# RS485.net
KiCad netlist of a schematic drawn in Altium Designer
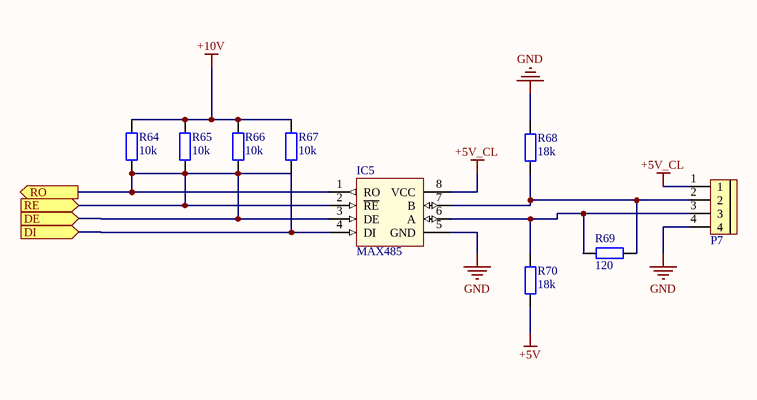
[diagram p0: RS485.SchDoc]

(export (version "E")
  (design (tool "Eeschema 10.0.6"))
  (components
    (comp (ref "IC5")
      (value "MAX485")
      (footprint "SO-8N")
      (description "RS232 - RS485 (Same sn75176)")
      (libsource (lib "My library altium") (part "MAX485"))
    )
    (comp (ref "P7")
      (value "CON 4 EDG5.08")
      (footprint "CON 4 4EDG5.08")
      (description "Cắm")
      (libsource (lib "Altium_Lib_by_KhueNguyenCreator") (part "CON 4 EDG5.08"))
    )
    (comp (ref "R64")
      (value "10k")
      (footprint "tro smd 0805")
      (description "Dán")
      (libsource (lib "Altium_Lib_by_KhueNguyenCreator") (part "Tro 0805 1% 10k"))
    )
    (comp (ref "R65")
      (value "10k")
      (footprint "tro smd 0805")
      (description "Dán")
      (libsource (lib "Altium_Lib_by_KhueNguyenCreator") (part "Tro 0805 1% 10k"))
    )
    (comp (ref "R66")
      (value "10k")
      (footprint "tro smd 0805")
      (description "Dán")
      (libsource (lib "Altium_Lib_by_KhueNguyenCreator") (part "Tro 0805 1% 10k"))
    )
    (comp (ref "R67")
      (value "10k")
      (footprint "tro smd 0805")
      (description "Dán")
      (libsource (lib "Altium_Lib_by_KhueNguyenCreator") (part "Tro 0805 1% 10k"))
    )
    (comp (ref "R68")
      (value "18k")
      (footprint "tro smd 0805")
      (description "Dán")
      (libsource (lib "Altium_Lib_by_KhueNguyenCreator") (part "Tro 0805 1% 18k"))
    )
    (comp (ref "R69")
      (value "120")
      (footprint "tro smd 0805")
      (description "Dán")
      (libsource (lib "Altium_Lib_by_KhueNguyenCreator") (part "Tro 0805 1% 12k"))
    )
    (comp (ref "R70")
      (value "18k")
      (footprint "tro smd 0805")
      (description "Dán")
      (libsource (lib "Altium_Lib_by_KhueNguyenCreator") (part "Tro 0805 1% 18k"))
    )
  )
  (nets
    (net (code "1") (name "+5V") (class "Default")
      (node (ref "R70") (pin "1") (pinfunction "1_1") (pintype "passive"))
    )
    (net (code "2") (name "+5V_CL") (class "Default")
      (node (ref "IC5") (pin "8") (pinfunction "VCC_8") (pintype "passive"))
      (node (ref "P7") (pin "1") (pinfunction "1_1") (pintype "passive"))
    )
    (net (code "3") (name "+10V") (class "Default")
      (node (ref "R64") (pin "2") (pinfunction "2_2") (pintype "passive"))
      (node (ref "R65") (pin "2") (pinfunction "2_2") (pintype "passive"))
      (node (ref "R66") (pin "2") (pinfunction "2_2") (pintype "passive"))
      (node (ref "R67") (pin "2") (pinfunction "2_2") (pintype "passive"))
    )
    (net (code "4") (name "/DE") (class "Default")
      (node (ref "IC5") (pin "1") (pinfunction "RO_1") (pintype "output"))
      (node (ref "IC5") (pin "2") (pinfunction "~{RE}_2") (pintype "input"))
      (node (ref "IC5") (pin "3") (pinfunction "DE_3") (pintype "input"))
      (node (ref "IC5") (pin "4") (pinfunction "DI_4") (pintype "input"))
      (node (ref "R64") (pin "1") (pinfunction "1_1") (pintype "passive"))
      (node (ref "R65") (pin "1") (pinfunction "1_1") (pintype "passive"))
      (node (ref "R66") (pin "1") (pinfunction "1_1") (pintype "passive"))
      (node (ref "R67") (pin "1") (pinfunction "1_1") (pintype "passive"))
    )
    (net (code "5") (name "GND") (class "Default")
      (node (ref "IC5") (pin "5") (pinfunction "GND_5") (pintype "passive"))
      (node (ref "P7") (pin "4") (pinfunction "4_4") (pintype "passive"))
      (node (ref "R68") (pin "2") (pinfunction "2_2") (pintype "passive"))
    )
    (net (code "6") (name "Net-(IC5-A)") (class "Default")
      (node (ref "IC5") (pin "6") (pinfunction "A_6") (pintype "bidirectional"))
      (node (ref "P7") (pin "3") (pinfunction "3_3") (pintype "passive"))
      (node (ref "R69") (pin "1") (pinfunction "1_1") (pintype "passive"))
      (node (ref "R70") (pin "2") (pinfunction "2_2") (pintype "passive"))
    )
    (net (code "7") (name "Net-(IC5-B)") (class "Default")
      (node (ref "IC5") (pin "7") (pinfunction "B_7") (pintype "bidirectional"))
      (node (ref "P7") (pin "2") (pinfunction "2_2") (pintype "passive"))
      (node (ref "R68") (pin "1") (pinfunction "1_1") (pintype "passive"))
      (node (ref "R69") (pin "2") (pinfunction "2_2") (pintype "passive"))
    )
  )
)
